# p2n-001.net
KiCad netlist of a schematic drawn in EAGLE
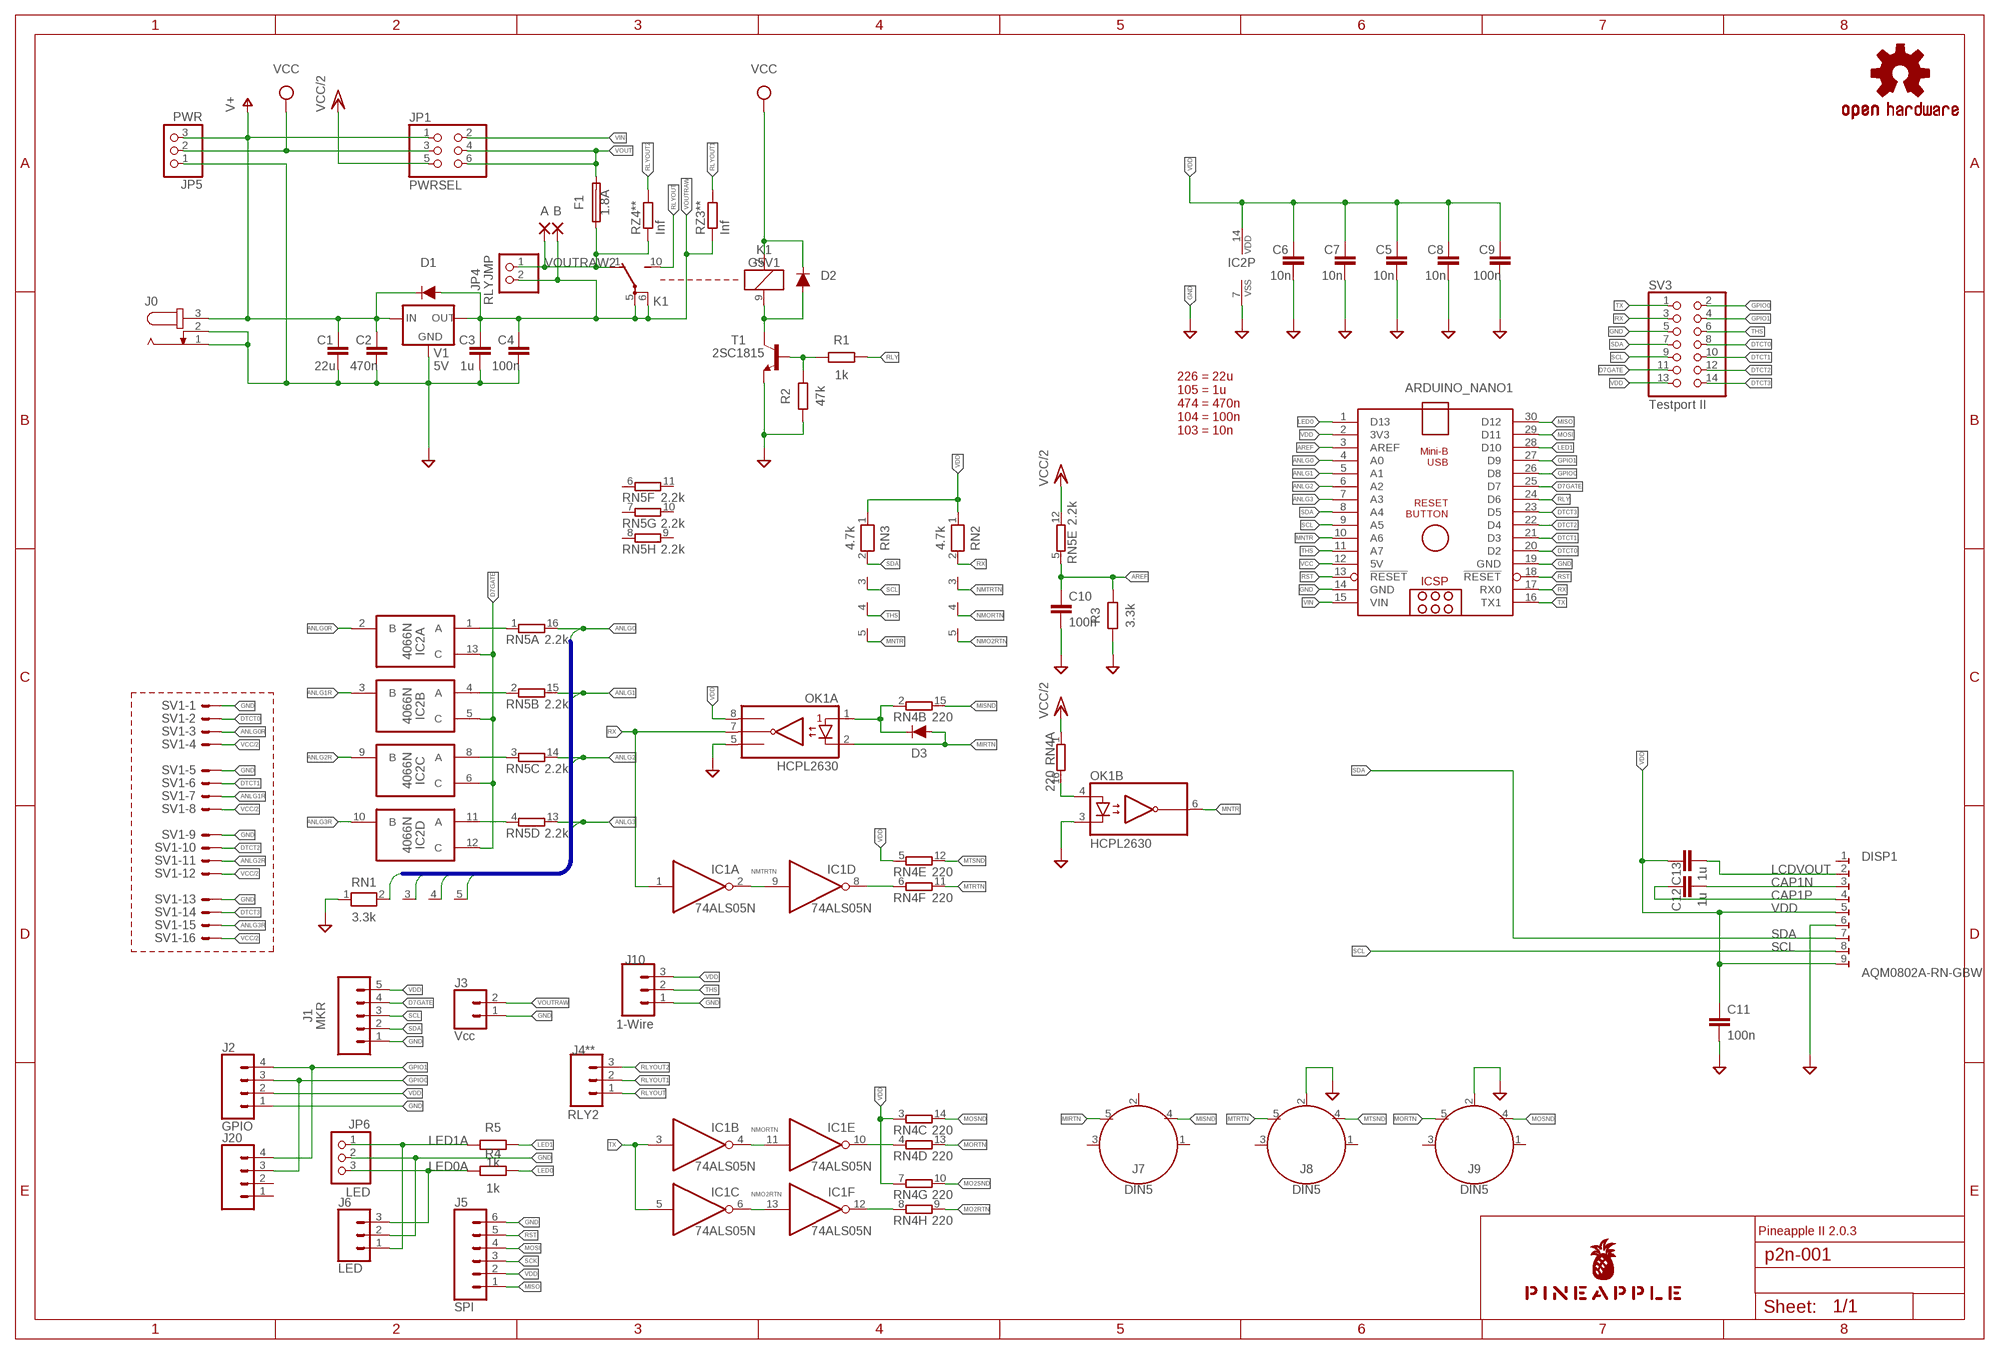
[diagram p0: schematic, sheet 1]

(export (version "E")
  (design (tool "Eeschema 10.0.6"))
  (components
    (comp (ref "A")
      (value "SMD2")
      (footprint "eagle-import:SMD1,27-2,54")
      (libsource (lib "eagle-import") (part "SMD2"))
    )
    (comp (ref "ARDUINO_NANO1")
      (value "ARDUINO_NANO")
      (footprint "eagle-import:ARDUINO_NANO")
      (libsource (lib "eagle-import") (part "ARDUINO_NANO"))
    )
    (comp (ref "B")
      (value "SMD2")
      (footprint "eagle-import:SMD1,27-2,54")
      (libsource (lib "eagle-import") (part "SMD2"))
    )
    (comp (ref "C1")
      (value "22u")
      (footprint "eagle-import:C025-050X050")
      (libsource (lib "eagle-import") (part "C-EU025-050X050"))
    )
    (comp (ref "C2")
      (value "470n")
      (footprint "eagle-import:C050-024X044")
      (libsource (lib "eagle-import") (part "C-EU050-024X044"))
    )
    (comp (ref "C3")
      (value "1u")
      (footprint "eagle-import:C050-024X044")
      (libsource (lib "eagle-import") (part "C-EU050-024X044"))
    )
    (comp (ref "C4")
      (value "100n")
      (footprint "eagle-import:C025-024X044")
      (libsource (lib "eagle-import") (part "C-EU025-024X044"))
    )
    (comp (ref "C5")
      (value "10n")
      (footprint "eagle-import:C025-024X044")
      (libsource (lib "eagle-import") (part "resistor_348_C-EU025-024X044"))
    )
    (comp (ref "C6")
      (value "10n")
      (footprint "eagle-import:C025-024X044")
      (libsource (lib "eagle-import") (part "resistor_348_C-EU025-024X044"))
    )
    (comp (ref "C7")
      (value "10n")
      (footprint "eagle-import:C025-024X044")
      (libsource (lib "eagle-import") (part "resistor_348_C-EU025-024X044"))
    )
    (comp (ref "C8")
      (value "10n")
      (footprint "eagle-import:C025-024X044")
      (libsource (lib "eagle-import") (part "resistor_348_C-EU025-024X044"))
    )
    (comp (ref "C9")
      (value "100n")
      (footprint "eagle-import:C025-024X044")
      (libsource (lib "eagle-import") (part "resistor_348_C-EU025-024X044"))
    )
    (comp (ref "C10")
      (value "100n")
      (footprint "eagle-import:C025-024X044")
      (libsource (lib "eagle-import") (part "C-EU025-024X044"))
    )
    (comp (ref "C11")
      (value "100n")
      (footprint "eagle-import:C025-024X044")
      (libsource (lib "eagle-import") (part "C-EU025-024X044"))
    )
    (comp (ref "C12")
      (value "1u")
      (footprint "eagle-import:C050-024X044")
      (libsource (lib "eagle-import") (part "C-EU050-024X044"))
    )
    (comp (ref "C13")
      (value "1u")
      (footprint "eagle-import:C050-024X044")
      (libsource (lib "eagle-import") (part "C-EU050-024X044"))
    )
    (comp (ref "D1")
      (value "DIODE-1N4148")
      (footprint "eagle-import:DIODE-1N4148")
      (libsource (lib "eagle-import") (part "DIODE-1N4148"))
    )
    (comp (ref "D2")
      (value "DIODE-1N4148")
      (footprint "eagle-import:DIODE-1N4148")
      (libsource (lib "eagle-import") (part "DIODE-1N4148"))
    )
    (comp (ref "D3")
      (value "DIODE-1N4148")
      (footprint "eagle-import:DIODE-1N4148")
      (libsource (lib "eagle-import") (part "DIODE-1N4148"))
    )
    (comp (ref "DISP1")
      (value "AQM0802A-RN-GBW")
      (footprint "eagle-import:AQM0802A-RN-GBW-FOOTPRINT")
      (libsource (lib "eagle-import") (part "AQM0802A-RN-GBW"))
    )
    (comp (ref "F1")
      (value "1.8A")
      (footprint "eagle-import:TE5")
      (libsource (lib "eagle-import") (part "TE5"))
    )
    (comp (ref "IC1")
      (value "74ALS05N")
      (footprint "eagle-import:DIL14")
      (libsource (lib "eagle-import") (part "7405NALS"))
    )
    (comp (ref "IC2")
      (value "4066N")
      (footprint "eagle-import:DIL14")
      (libsource (lib "eagle-import") (part "4066N"))
    )
    (comp (ref "J0")
      (value "JACK-PLUG0")
      (footprint "eagle-import:SPC4077")
      (libsource (lib "eagle-import") (part "JACK-PLUG0"))
    )
    (comp (ref "J1")
      (value "MKR")
      (footprint "eagle-import:JST-5-PTH")
      (libsource (lib "eagle-import") (part "CONN_05JST"))
    )
    (comp (ref "J2")
      (value "GPIO")
      (footprint "eagle-import:JST-4-PTH")
      (libsource (lib "eagle-import") (part "CONN_04JST-PTH"))
    )
    (comp (ref "J3")
      (value "Vcc")
      (footprint "eagle-import:JST-2-PTH")
      (libsource (lib "eagle-import") (part "CONN_02JST-PTH-2"))
    )
    (comp (ref "J4**")
      (value "RLY2")
      (footprint "eagle-import:JST-3-PTH-NS")
      (libsource (lib "eagle-import") (part "CONN_03JST-PTH-NS"))
    )
    (comp (ref "J5")
      (value "SPI")
      (footprint "eagle-import:1X06_1.27MM")
      (libsource (lib "eagle-import") (part "CONN_061.27MM"))
    )
    (comp (ref "J6")
      (value "LED")
      (footprint "eagle-import:JST-3-PTH-VERT")
      (libsource (lib "eagle-import") (part "CONN_03JST-PTH-VERT"))
    )
    (comp (ref "J7")
      (value "DIN5")
      (footprint "eagle-import:DIN5-RA-PTH")
      (libsource (lib "eagle-import") (part "DIN5"))
    )
    (comp (ref "J8")
      (value "DIN5")
      (footprint "eagle-import:DIN5-RA-PTH")
      (libsource (lib "eagle-import") (part "DIN5"))
    )
    (comp (ref "J9")
      (value "DIN5")
      (footprint "eagle-import:DIN5-RA-PTH")
      (libsource (lib "eagle-import") (part "DIN5"))
    )
    (comp (ref "J10")
      (value "1-Wire")
      (footprint "eagle-import:JST-3-PTH-VERT")
      (libsource (lib "eagle-import") (part "CONN_03JST-PTH-VERT"))
    )
    (comp (ref "J20")
      (value "CONN_041.27MM")
      (footprint "eagle-import:1X04_1.27MM")
      (libsource (lib "eagle-import") (part "CONN_041.27MM"))
    )
    (comp (ref "JP1")
      (value "PWRSEL")
      (footprint "eagle-import:2X03")
      (libsource (lib "eagle-import") (part "PINHD-2X3"))
    )
    (comp (ref "JP4")
      (value "RLYJMP")
      (footprint "eagle-import:1X02")
      (libsource (lib "eagle-import") (part "PINHD-1X2"))
    )
    (comp (ref "JP5")
      (value "PWR")
      (footprint "eagle-import:1X03")
      (libsource (lib "eagle-import") (part "PINHD-1X3"))
    )
    (comp (ref "JP6")
      (value "LED")
      (footprint "eagle-import:1X03")
      (libsource (lib "eagle-import") (part "PINHD-1X3"))
    )
    (comp (ref "K1")
      (value "G5V1")
      (footprint "eagle-import:G5V1")
      (fields (field (name "MPN") "G5V-1-DC24"))
      (libsource (lib "eagle-import") (part "G5V1"))
    )
    (comp (ref "LOGO1")
      (value "OSHW-LOGOS-COPPER")
      (footprint "eagle-import:OSHW-LOGO-S_COPPER")
      (libsource (lib "eagle-import") (part "OSHW-LOGOS-COPPER"))
    )
    (comp (ref "OK1")
      (value "HCPL2630")
      (footprint "eagle-import:DIL08")
      (fields (field (name "MF") "AGILENT TECHNOLOGIES") (field (name "MPN") "HCPL-2630-000E"))
      (libsource (lib "eagle-import") (part "HCPL2630"))
    )
    (comp (ref "R1")
      (value "1k")
      (footprint "eagle-import:0204_5")
      (libsource (lib "eagle-import") (part "resistor_348_R-EU_0204/5"))
    )
    (comp (ref "R2")
      (value "47k")
      (footprint "eagle-import:0204_5")
      (libsource (lib "eagle-import") (part "resistor_348_R-EU_0204/5"))
    )
    (comp (ref "R3")
      (value "3.3k")
      (footprint "eagle-import:0204_5")
      (libsource (lib "eagle-import") (part "resistor_348_R-EU_0204/5"))
    )
    (comp (ref "R4")
      (value "1k")
      (footprint "eagle-import:0204_5")
      (libsource (lib "eagle-import") (part "resistor_348_R-EU_0204/5"))
    )
    (comp (ref "R5")
      (value "1k")
      (footprint "eagle-import:0204_5")
      (libsource (lib "eagle-import") (part "resistor_348_R-EU_0204/5"))
    )
    (comp (ref "RN1")
      (value "3.3k")
      (footprint "eagle-import:RN-5")
      (libsource (lib "eagle-import") (part "RN04"))
    )
    (comp (ref "RN2")
      (value "4.7k")
      (footprint "eagle-import:RN-5")
      (libsource (lib "eagle-import") (part "RN04"))
    )
    (comp (ref "RN3")
      (value "4.7k")
      (footprint "eagle-import:RN-5")
      (libsource (lib "eagle-import") (part "RN04"))
    )
    (comp (ref "RN4")
      (value "220")
      (footprint "eagle-import:DIL16")
      (libsource (lib "eagle-import") (part "8R-N"))
    )
    (comp (ref "RN5")
      (value "2.2k")
      (footprint "eagle-import:DIL16")
      (libsource (lib "eagle-import") (part "8R-N"))
    )
    (comp (ref "RZ3**")
      (value "Inf")
      (footprint "eagle-import:M2012")
      (libsource (lib "eagle-import") (part "R-EU_M2012"))
    )
    (comp (ref "RZ4**")
      (value "Inf")
      (footprint "eagle-import:M2012")
      (libsource (lib "eagle-import") (part "R-EU_M2012"))
    )
    (comp (ref "SV1")
      (value "ML16LE")
      (footprint "eagle-import:ML16L")
      (libsource (lib "eagle-import") (part "ML16LE"))
    )
    (comp (ref "SV3")
      (value "Testport II")
      (footprint "eagle-import:2X07")
      (libsource (lib "eagle-import") (part "PINHD-2X7"))
    )
    (comp (ref "T1")
      (value "2SC1815")
      (footprint "eagle-import:TO92-ECB")
      (libsource (lib "eagle-import") (part "2SC1815"))
    )
    (comp (ref "U$1")
      (value "PINEAPPLE450_SILK")
      (footprint "eagle-import:PINEAPPLE450_SILK")
      (libsource (lib "eagle-import") (part "PINEAPPLE450_SILK"))
    )
    (comp (ref "V1")
      (value "5V")
      (footprint "eagle-import:78XXL")
      (libsource (lib "eagle-import") (part "78XXL"))
    )
  )
  (nets
    (net (code "1") (name "/CAP1N") (class "Default")
      (node (ref "C12") (pin "2") (pinfunction "2_2") (pintype "passive"))
      (node (ref "DISP1") (pin "3") (pinfunction "3_3") (pintype "passive"))
    )
    (net (code "2") (name "/CAP1P") (class "Default")
      (node (ref "C12") (pin "1") (pinfunction "1_1") (pintype "passive"))
      (node (ref "DISP1") (pin "4") (pinfunction "4_4") (pintype "passive"))
    )
    (net (code "3") (name "/LCDVOUT") (class "Default")
      (node (ref "C13") (pin "2") (pinfunction "2_2") (pintype "passive"))
      (node (ref "DISP1") (pin "2") (pinfunction "2_2") (pintype "passive"))
    )
    (net (code "4") (name "/LED0A") (class "Default")
      (node (ref "J6") (pin "3") (pinfunction "3_3") (pintype "passive"))
      (node (ref "JP6") (pin "3") (pinfunction "3_3") (pintype "passive"))
      (node (ref "R4") (pin "1") (pinfunction "1_1") (pintype "passive"))
    )
    (net (code "5") (name "/LED1A") (class "Default")
      (node (ref "J6") (pin "1") (pinfunction "1_1") (pintype "passive"))
      (node (ref "JP6") (pin "1") (pinfunction "1_1") (pintype "passive"))
      (node (ref "R5") (pin "1") (pinfunction "1_1") (pintype "passive"))
    )
    (net (code "6") (name "/VOUTRAW2") (class "Default")
      (node (ref "A") (pin "1") (pinfunction "P_1") (pintype "passive"))
      (node (ref "F1") (pin "1") (pinfunction "1_1") (pintype "passive"))
      (node (ref "JP4") (pin "1") (pinfunction "1_1") (pintype "passive"))
      (node (ref "K1") (pin "1") (pinfunction "O_1") (pintype "passive"))
      (node (ref "RZ4**") (pin "1") (pinfunction "1_1") (pintype "passive"))
    )
    (net (code "7") (name "ANLG0") (class "Default")
      (node (ref "ARDUINO_NANO1") (pin "4") (pinfunction "A0_4") (pintype "bidirectional"))
      (node (ref "RN1") (pin "2") (pinfunction "2_2") (pintype "passive"))
      (node (ref "RN5") (pin "16") (pinfunction "2_16") (pintype "passive"))
    )
    (net (code "8") (name "ANLG0R") (class "Default")
      (node (ref "IC2") (pin "2") (pinfunction "B_2") (pintype "tri_state"))
      (node (ref "SV1") (pin "3") (pinfunction "S_3") (pintype "passive"))
    )
    (net (code "9") (name "ANLG1") (class "Default")
      (node (ref "ARDUINO_NANO1") (pin "5") (pinfunction "A1_5") (pintype "bidirectional"))
      (node (ref "RN1") (pin "3") (pinfunction "3_3") (pintype "passive"))
      (node (ref "RN5") (pin "15") (pinfunction "2_15") (pintype "passive"))
    )
    (net (code "10") (name "ANLG1R") (class "Default")
      (node (ref "IC2") (pin "3") (pinfunction "B_3") (pintype "tri_state"))
      (node (ref "SV1") (pin "7") (pinfunction "S_7") (pintype "passive"))
    )
    (net (code "11") (name "ANLG2") (class "Default")
      (node (ref "ARDUINO_NANO1") (pin "6") (pinfunction "A2_6") (pintype "bidirectional"))
      (node (ref "RN1") (pin "4") (pinfunction "4_4") (pintype "passive"))
      (node (ref "RN5") (pin "14") (pinfunction "2_14") (pintype "passive"))
    )
    (net (code "12") (name "ANLG2R") (class "Default")
      (node (ref "IC2") (pin "9") (pinfunction "B_9") (pintype "tri_state"))
      (node (ref "SV1") (pin "11") (pinfunction "S_11") (pintype "passive"))
    )
    (net (code "13") (name "ANLG3") (class "Default")
      (node (ref "ARDUINO_NANO1") (pin "7") (pinfunction "A3_7") (pintype "bidirectional"))
      (node (ref "RN1") (pin "5") (pinfunction "5_5") (pintype "passive"))
      (node (ref "RN5") (pin "13") (pinfunction "2_13") (pintype "passive"))
    )
    (net (code "14") (name "ANLG3R") (class "Default")
      (node (ref "IC2") (pin "10") (pinfunction "B_10") (pintype "tri_state"))
      (node (ref "SV1") (pin "15") (pinfunction "S_15") (pintype "passive"))
    )
    (net (code "15") (name "AREF") (class "Default")
      (node (ref "ARDUINO_NANO1") (pin "3") (pinfunction "AREF_3") (pintype "input"))
      (node (ref "C10") (pin "1") (pinfunction "1_1") (pintype "passive"))
      (node (ref "R3") (pin "2") (pinfunction "2_2") (pintype "passive"))
      (node (ref "RN5") (pin "5") (pinfunction "1_5") (pintype "passive"))
    )
    (net (code "16") (name "D7GATE") (class "Default")
      (node (ref "ARDUINO_NANO1") (pin "25") (pinfunction "D7_25") (pintype "bidirectional"))
      (node (ref "IC2") (pin "12") (pinfunction "C_12") (pintype "input"))
      (node (ref "IC2") (pin "13") (pinfunction "C_13") (pintype "input"))
      (node (ref "IC2") (pin "5") (pinfunction "C_5") (pintype "input"))
      (node (ref "IC2") (pin "6") (pinfunction "C_6") (pintype "input"))
      (node (ref "J1") (pin "4") (pinfunction "4_4") (pintype "passive"))
      (node (ref "SV3") (pin "11") (pinfunction "11_11") (pintype "passive"))
    )
    (net (code "17") (name "DTCT0") (class "Default")
      (node (ref "ARDUINO_NANO1") (pin "20") (pinfunction "D2_20") (pintype "bidirectional"))
      (node (ref "SV1") (pin "2") (pinfunction "S_2") (pintype "passive"))
      (node (ref "SV3") (pin "8") (pinfunction "8_8") (pintype "passive"))
    )
    (net (code "18") (name "DTCT1") (class "Default")
      (node (ref "ARDUINO_NANO1") (pin "21") (pinfunction "D3_21") (pintype "bidirectional"))
      (node (ref "SV1") (pin "6") (pinfunction "S_6") (pintype "passive"))
      (node (ref "SV3") (pin "10") (pinfunction "10_10") (pintype "passive"))
    )
    (net (code "19") (name "DTCT2") (class "Default")
      (node (ref "ARDUINO_NANO1") (pin "22") (pinfunction "D4_22") (pintype "bidirectional"))
      (node (ref "SV1") (pin "10") (pinfunction "S_10") (pintype "passive"))
      (node (ref "SV3") (pin "12") (pinfunction "12_12") (pintype "passive"))
    )
    (net (code "20") (name "DTCT3") (class "Default")
      (node (ref "ARDUINO_NANO1") (pin "23") (pinfunction "D5_23") (pintype "bidirectional"))
      (node (ref "SV1") (pin "14") (pinfunction "S_14") (pintype "passive"))
      (node (ref "SV3") (pin "14") (pinfunction "14_14") (pintype "passive"))
    )
    (net (code "21") (name "GND") (class "Default")
      (node (ref "ARDUINO_NANO1") (pin "14") (pinfunction "GND_14") (pintype "power_in"))
      (node (ref "ARDUINO_NANO1") (pin "19") (pinfunction "GND_19") (pintype "power_in"))
      (node (ref "C1") (pin "2") (pinfunction "2_2") (pintype "passive"))
      (node (ref "C10") (pin "2") (pinfunction "2_2") (pintype "passive"))
      (node (ref "C11") (pin "2") (pinfunction "2_2") (pintype "passive"))
      (node (ref "C2") (pin "2") (pinfunction "2_2") (pintype "passive"))
      (node (ref "C3") (pin "2") (pinfunction "2_2") (pintype "passive"))
      (node (ref "C4") (pin "2") (pinfunction "2_2") (pintype "passive"))
      (node (ref "C5") (pin "2") (pinfunction "2_2") (pintype "passive"))
      (node (ref "C6") (pin "2") (pinfunction "2_2") (pintype "passive"))
      (node (ref "C7") (pin "2") (pinfunction "2_2") (pintype "passive"))
      (node (ref "C8") (pin "2") (pinfunction "2_2") (pintype "passive"))
      (node (ref "C9") (pin "2") (pinfunction "2_2") (pintype "passive"))
      (node (ref "DISP1") (pin "6") (pinfunction "6_6") (pintype "passive"))
      (node (ref "IC2") (pin "7") (pinfunction "VSS_7") (pintype "power_in"))
      (node (ref "J0") (pin "1") (pinfunction "1_1") (pintype "passive"))
      (node (ref "J0") (pin "2") (pinfunction "2_2") (pintype "passive"))
      (node (ref "J1") (pin "1") (pinfunction "1_1") (pintype "passive"))
      (node (ref "J10") (pin "1") (pinfunction "1_1") (pintype "passive"))
      (node (ref "J2") (pin "1") (pinfunction "1_1") (pintype "passive"))
      (node (ref "J3") (pin "1") (pinfunction "1_1") (pintype "passive"))
      (node (ref "J5") (pin "6") (pinfunction "6_6") (pintype "passive"))
      (node (ref "J6") (pin "2") (pinfunction "2_2") (pintype "passive"))
      (node (ref "J8") (pin "2") (pinfunction "2_2") (pintype "bidirectional"))
      (node (ref "J9") (pin "2") (pinfunction "2_2") (pintype "bidirectional"))
      (node (ref "JP5") (pin "1") (pinfunction "1_1") (pintype "passive"))
      (node (ref "JP6") (pin "2") (pinfunction "2_2") (pintype "passive"))
      (node (ref "OK1") (pin "3") (pinfunction "C2_3") (pintype "passive"))
      (node (ref "OK1") (pin "5") (pinfunction "GND_5") (pintype "passive"))
      (node (ref "R2") (pin "1") (pinfunction "1_1") (pintype "passive"))
      (node (ref "R3") (pin "1") (pinfunction "1_1") (pintype "passive"))
      (node (ref "RN1") (pin "1") (pinfunction "1_1") (pintype "passive"))
      (node (ref "SV1") (pin "1") (pinfunction "S_1") (pintype "passive"))
      (node (ref "SV1") (pin "13") (pinfunction "S_13") (pintype "passive"))
      (node (ref "SV1") (pin "5") (pinfunction "S_5") (pintype "passive"))
      (node (ref "SV1") (pin "9") (pinfunction "S_9") (pintype "passive"))
      (node (ref "SV3") (pin "5") (pinfunction "5_5") (pintype "passive"))
      (node (ref "T1") (pin "E") (pinfunction "E_E") (pintype "passive"))
      (node (ref "V1") (pin "GND") (pinfunction "GND_GND") (pintype "input"))
    )
    (net (code "22") (name "GPIO0") (class "Default")
      (node (ref "ARDUINO_NANO1") (pin "26") (pinfunction "D8_26") (pintype "bidirectional"))
      (node (ref "J2") (pin "3") (pinfunction "3_3") (pintype "passive"))
      (node (ref "J20") (pin "3") (pinfunction "3_3") (pintype "passive"))
      (node (ref "SV3") (pin "2") (pinfunction "2_2") (pintype "passive"))
    )
    (net (code "23") (name "GPIO1") (class "Default")
      (node (ref "ARDUINO_NANO1") (pin "27") (pinfunction "D9_27") (pintype "bidirectional"))
      (node (ref "J2") (pin "4") (pinfunction "4_4") (pintype "passive"))
      (node (ref "J20") (pin "4") (pinfunction "4_4") (pintype "passive"))
      (node (ref "SV3") (pin "4") (pinfunction "4_4") (pintype "passive"))
    )
    (net (code "24") (name "LED0") (class "Default")
      (node (ref "ARDUINO_NANO1") (pin "1") (pinfunction "D13_1") (pintype "bidirectional"))
      (node (ref "R4") (pin "2") (pinfunction "2_2") (pintype "passive"))
    )
    (net (code "25") (name "LED1") (class "Default")
      (node (ref "ARDUINO_NANO1") (pin "28") (pinfunction "D10_28") (pintype "bidirectional"))
      (node (ref "R5") (pin "2") (pinfunction "2_2") (pintype "passive"))
    )
    (net (code "26") (name "MIRTN") (class "Default")
      (node (ref "D3") (pin "A") (pinfunction "A_A") (pintype "passive"))
      (node (ref "J7") (pin "5") (pinfunction "5_5") (pintype "bidirectional"))
      (node (ref "OK1") (pin "2") (pinfunction "C1_2") (pintype "passive"))
    )
    (net (code "27") (name "MISND") (class "Default")
      (node (ref "J7") (pin "4") (pinfunction "4_4") (pintype "bidirectional"))
      (node (ref "RN4") (pin "15") (pinfunction "2_15") (pintype "passive"))
    )
    (net (code "28") (name "MISO") (class "Default")
      (node (ref "ARDUINO_NANO1") (pin "30") (pinfunction "D12_30") (pintype "bidirectional"))
      (node (ref "J5") (pin "1") (pinfunction "1_1") (pintype "passive"))
    )
    (net (code "29") (name "MNTR") (class "Default")
      (node (ref "ARDUINO_NANO1") (pin "10") (pinfunction "A6_10") (pintype "bidirectional"))
      (node (ref "OK1") (pin "6") (pinfunction "VO2_6") (pintype "passive"))
      (node (ref "RN3") (pin "5") (pinfunction "5_5") (pintype "passive"))
    )
    (net (code "30") (name "MO2RTN") (class "Default")
      (node (ref "RN4") (pin "9") (pinfunction "2_9") (pintype "passive"))
    )
    (net (code "31") (name "MO2SND") (class "Default")
      (node (ref "RN4") (pin "10") (pinfunction "2_10") (pintype "passive"))
    )
    (net (code "32") (name "MORTN") (class "Default")
      (node (ref "J9") (pin "5") (pinfunction "5_5") (pintype "bidirectional"))
      (node (ref "RN4") (pin "13") (pinfunction "2_13") (pintype "passive"))
    )
    (net (code "33") (name "MOSI") (class "Default")
      (node (ref "ARDUINO_NANO1") (pin "29") (pinfunction "D11_29") (pintype "bidirectional"))
      (node (ref "J5") (pin "4") (pinfunction "4_4") (pintype "passive"))
    )
    (net (code "34") (name "MOSND") (class "Default")
      (node (ref "J9") (pin "4") (pinfunction "4_4") (pintype "bidirectional"))
      (node (ref "RN4") (pin "14") (pinfunction "2_14") (pintype "passive"))
    )
    (net (code "35") (name "MTRTN") (class "Default")
      (node (ref "J8") (pin "5") (pinfunction "5_5") (pintype "bidirectional"))
      (node (ref "RN4") (pin "11") (pinfunction "2_11") (pintype "passive"))
    )
    (net (code "36") (name "MTSND") (class "Default")
      (node (ref "J8") (pin "4") (pinfunction "4_4") (pintype "bidirectional"))
      (node (ref "RN4") (pin "12") (pinfunction "2_12") (pintype "passive"))
    )
    (net (code "37") (name "NMO2RTN") (class "Default")
      (node (ref "IC1") (pin "13") (pinfunction "I_13") (pintype "input"))
      (node (ref "IC1") (pin "6") (pinfunction "O_6") (pintype "open_collector"))
      (node (ref "RN2") (pin "5") (pinfunction "5_5") (pintype "passive"))
    )
    (net (code "38") (name "NMORTN") (class "Default")
      (node (ref "IC1") (pin "11") (pinfunction "I_11") (pintype "input"))
      (node (ref "IC1") (pin "4") (pinfunction "O_4") (pintype "open_collector"))
      (node (ref "RN2") (pin "4") (pinfunction "4_4") (pintype "passive"))
    )
    (net (code "39") (name "NMTRTN") (class "Default")
      (node (ref "IC1") (pin "2") (pinfunction "O_2") (pintype "open_collector"))
      (node (ref "IC1") (pin "9") (pinfunction "I_9") (pintype "input"))
      (node (ref "RN2") (pin "3") (pinfunction "3_3") (pintype "passive"))
    )
    (net (code "40") (name "Net-(IC1D-O)") (class "Default")
      (node (ref "IC1") (pin "8") (pinfunction "O_8") (pintype "open_collector"))
      (node (ref "RN4") (pin "6") (pinfunction "1_6") (pintype "passive"))
    )
    (net (code "41") (name "Net-(IC1E-O)") (class "Default")
      (node (ref "IC1") (pin "10") (pinfunction "O_10") (pintype "open_collector"))
      (node (ref "RN4") (pin "4") (pinfunction "1_4") (pintype "passive"))
    )
    (net (code "42") (name "Net-(IC1F-O)") (class "Default")
      (node (ref "IC1") (pin "12") (pinfunction "O_12") (pintype "open_collector"))
      (node (ref "RN4") (pin "8") (pinfunction "1_8") (pintype "passive"))
    )
    (net (code "43") (name "Net-(IC2A-A)") (class "Default")
      (node (ref "IC2") (pin "1") (pinfunction "A_1") (pintype "tri_state"))
      (node (ref "RN5") (pin "1") (pinfunction "1_1") (pintype "passive"))
    )
    (net (code "44") (name "Net-(IC2B-A)") (class "Default")
      (node (ref "IC2") (pin "4") (pinfunction "A_4") (pintype "tri_state"))
      (node (ref "RN5") (pin "2") (pinfunction "1_2") (pintype "passive"))
    )
    (net (code "45") (name "Net-(IC2C-A)") (class "Default")
      (node (ref "IC2") (pin "8") (pinfunction "A_8") (pintype "tri_state"))
      (node (ref "RN5") (pin "3") (pinfunction "1_3") (pintype "passive"))
    )
    (net (code "46") (name "Net-(IC2D-A)") (class "Default")
      (node (ref "IC2") (pin "11") (pinfunction "A_11") (pintype "tri_state"))
      (node (ref "RN5") (pin "4") (pinfunction "1_4") (pintype "passive"))
    )
    (net (code "47") (name "Net-(K1A-2)") (class "Default")
      (node (ref "D2") (pin "A") (pinfunction "A_A") (pintype "passive"))
      (node (ref "K1") (pin "9") (pinfunction "2_9") (pintype "passive"))
      (node (ref "T1") (pin "C") (pinfunction "C_C") (pintype "passive"))
    )
    (net (code "48") (name "Net-(OK1A-A1)") (class "Default")
      (node (ref "D3") (pin "C") (pinfunction "C_C") (pintype "passive"))
      (node (ref "OK1") (pin "1") (pinfunction "A1_1") (pintype "passive"))
      (node (ref "RN4") (pin "2") (pinfunction "1_2") (pintype "passive"))
    )
    (net (code "49") (name "Net-(OK1B-A2)") (class "Default")
      (node (ref "OK1") (pin "4") (pinfunction "A2_4") (pintype "passive"))
      (node (ref "RN4") (pin "16") (pinfunction "2_16") (pintype "passive"))
    )
    (net (code "50") (name "Net-(R1-Pad1)") (class "Default")
      (node (ref "R1") (pin "1") (pinfunction "1_1") (pintype "passive"))
      (node (ref "R2") (pin "2") (pinfunction "2_2") (pintype "passive"))
      (node (ref "T1") (pin "B") (pinfunction "B_B") (pintype "passive"))
    )
    (net (code "51") (name "RLY") (class "Default")
      (node (ref "ARDUINO_NANO1") (pin "24") (pinfunction "D6_24") (pintype "bidirectional"))
      (node (ref "R1") (pin "2") (pinfunction "2_2") (pintype "passive"))
    )
    (net (code "52") (name "RLYOUT") (class "Default")
      (node (ref "J4**") (pin "1") (pinfunction "1_1") (pintype "passive"))
      (node (ref "K1") (pin "10") (pinfunction "S_10") (pintype "passive"))
    )
    (net (code "53") (name "RLYOUT1") (class "Default")
      (node (ref "J4**") (pin "2") (pinfunction "2_2") (pintype "passive"))
      (node (ref "RZ3**") (pin "2") (pinfunction "2_2") (pintype "passive"))
    )
    (net (code "54") (name "RLYOUT2") (class "Default")
      (node (ref "J4**") (pin "3") (pinfunction "3_3") (pintype "passive"))
      (node (ref "RZ4**") (pin "2") (pinfunction "2_2") (pintype "passive"))
    )
    (net (code "55") (name "RST") (class "Default")
      (node (ref "ARDUINO_NANO1") (pin "13") (pinfunction "~{RESET}_13") (pintype "input"))
      (node (ref "ARDUINO_NANO1") (pin "18") (pinfunction "~{RESET}_18") (pintype "input"))
      (node (ref "J5") (pin "5") (pinfunction "5_5") (pintype "passive"))
    )
    (net (code "56") (name "RX") (class "Default")
      (node (ref "ARDUINO_NANO1") (pin "17") (pinfunction "RX0_17") (pintype "bidirectional"))
      (node (ref "IC1") (pin "1") (pinfunction "I_1") (pintype "input"))
      (node (ref "OK1") (pin "7") (pinfunction "VO1_7") (pintype "passive"))
      (node (ref "RN2") (pin "2") (pinfunction "2_2") (pintype "passive"))
      (node (ref "SV3") (pin "3") (pinfunction "3_3") (pintype "passive"))
    )
    (net (code "57") (name "SCK") (class "Default")
      (node (ref "J5") (pin "3") (pinfunction "3_3") (pintype "passive"))
    )
    (net (code "58") (name "SCL") (class "Default")
      (node (ref "ARDUINO_NANO1") (pin "9") (pinfunction "A5_9") (pintype "bidirectional"))
      (node (ref "DISP1") (pin "8") (pinfunction "8_8") (pintype "passive"))
      (node (ref "J1") (pin "3") (pinfunction "3_3") (pintype "passive"))
      (node (ref "RN3") (pin "3") (pinfunction "3_3") (pintype "passive"))
      (node (ref "SV3") (pin "9") (pinfunction "9_9") (pintype "passive"))
    )
    (net (code "59") (name "SDA") (class "Default")
      (node (ref "ARDUINO_NANO1") (pin "8") (pinfunction "A4_8") (pintype "bidirectional"))
      (node (ref "DISP1") (pin "7") (pinfunction "7_7") (pintype "passive"))
      (node (ref "J1") (pin "2") (pinfunction "2_2") (pintype "passive"))
      (node (ref "RN3") (pin "2") (pinfunction "2_2") (pintype "passive"))
      (node (ref "SV3") (pin "7") (pinfunction "7_7") (pintype "passive"))
    )
    (net (code "60") (name "THS") (class "Default")
      (node (ref "ARDUINO_NANO1") (pin "11") (pinfunction "A7_11") (pintype "bidirectional"))
      (node (ref "J10") (pin "2") (pinfunction "2_2") (pintype "passive"))
      (node (ref "RN3") (pin "4") (pinfunction "4_4") (pintype "passive"))
      (node (ref "SV3") (pin "6") (pinfunction "6_6") (pintype "passive"))
    )
    (net (code "61") (name "TX") (class "Default")
      (node (ref "ARDUINO_NANO1") (pin "16") (pinfunction "TX1_16") (pintype "bidirectional"))
      (node (ref "IC1") (pin "3") (pinfunction "I_3") (pintype "input"))
      (node (ref "IC1") (pin "5") (pinfunction "I_5") (pintype "input"))
      (node (ref "SV3") (pin "1") (pinfunction "1_1") (pintype "passive"))
    )
    (net (code "62") (name "V+") (class "Default")
      (node (ref "C1") (pin "1") (pinfunction "1_1") (pintype "passive"))
      (node (ref "C2") (pin "1") (pinfunction "1_1") (pintype "passive"))
      (node (ref "D1") (pin "C") (pinfunction "C_C") (pintype "passive"))
      (node (ref "J0") (pin "3") (pinfunction "3_3") (pintype "passive"))
      (node (ref "JP1") (pin "1") (pinfunction "1_1") (pintype "passive"))
      (node (ref "JP5") (pin "3") (pinfunction "3_3") (pintype "passive"))
      (node (ref "V1") (pin "IN") (pinfunction "IN_IN") (pintype "input"))
    )
    (net (code "63") (name "VCC") (class "Default")
      (node (ref "ARDUINO_NANO1") (pin "12") (pinfunction "5V_12") (pintype "power_in"))
      (node (ref "D2") (pin "C") (pinfunction "C_C") (pintype "passive"))
      (node (ref "JP1") (pin "3") (pinfunction "3_3") (pintype "passive"))
      (node (ref "JP5") (pin "2") (pinfunction "2_2") (pintype "passive"))
      (node (ref "K1") (pin "2") (pinfunction "1_2") (pintype "passive"))
    )
    (net (code "64") (name "VCC{slash}2") (class "Default")
      (node (ref "JP1") (pin "5") (pinfunction "5_5") (pintype "passive"))
      (node (ref "RN4") (pin "1") (pinfunction "1_1") (pintype "passive"))
      (node (ref "RN5") (pin "12") (pinfunction "2_12") (pintype "passive"))
      (node (ref "SV1") (pin "12") (pinfunction "S_12") (pintype "passive"))
      (node (ref "SV1") (pin "16") (pinfunction "S_16") (pintype "passive"))
      (node (ref "SV1") (pin "4") (pinfunction "S_4") (pintype "passive"))
      (node (ref "SV1") (pin "8") (pinfunction "S_8") (pintype "passive"))
    )
    (net (code "65") (name "VDD") (class "Default")
      (node (ref "ARDUINO_NANO1") (pin "2") (pinfunction "3V3_2") (pintype "output"))
      (node (ref "C11") (pin "1") (pinfunction "1_1") (pintype "passive"))
      (node (ref "C13") (pin "1") (pinfunction "1_1") (pintype "passive"))
      (node (ref "C5") (pin "1") (pinfunction "1_1") (pintype "passive"))
      (node (ref "C6") (pin "1") (pinfunction "1_1") (pintype "passive"))
      (node (ref "C7") (pin "1") (pinfunction "1_1") (pintype "passive"))
      (node (ref "C8") (pin "1") (pinfunction "1_1") (pintype "passive"))
      (node (ref "C9") (pin "1") (pinfunction "1_1") (pintype "passive"))
      (node (ref "DISP1") (pin "5") (pinfunction "5_5") (pintype "passive"))
      (node (ref "DISP1") (pin "9") (pinfunction "9_9") (pintype "passive"))
      (node (ref "IC2") (pin "14") (pinfunction "VDD_14") (pintype "power_in"))
      (node (ref "J1") (pin "5") (pinfunction "5_5") (pintype "passive"))
      (node (ref "J10") (pin "3") (pinfunction "3_3") (pintype "passive"))
      (node (ref "J2") (pin "2") (pinfunction "2_2") (pintype "passive"))
      (node (ref "J5") (pin "2") (pinfunction "2_2") (pintype "passive"))
      (node (ref "OK1") (pin "8") (pinfunction "VCC_8") (pintype "passive"))
      (node (ref "RN2") (pin "1") (pinfunction "1_1") (pintype "passive"))
      (node (ref "RN3") (pin "1") (pinfunction "1_1") (pintype "passive"))
      (node (ref "RN4") (pin "3") (pinfunction "1_3") (pintype "passive"))
      (node (ref "RN4") (pin "5") (pinfunction "1_5") (pintype "passive"))
      (node (ref "RN4") (pin "7") (pinfunction "1_7") (pintype "passive"))
      (node (ref "SV3") (pin "13") (pinfunction "13_13") (pintype "passive"))
    )
    (net (code "66") (name "VIN") (class "Default")
      (node (ref "ARDUINO_NANO1") (pin "15") (pinfunction "VIN_15") (pintype "power_in"))
      (node (ref "JP1") (pin "2") (pinfunction "2_2") (pintype "passive"))
    )
    (net (code "67") (name "VOUT") (class "Default")
      (node (ref "F1") (pin "2") (pinfunction "2_2") (pintype "passive"))
      (node (ref "JP1") (pin "4") (pinfunction "4_4") (pintype "passive"))
      (node (ref "JP1") (pin "6") (pinfunction "6_6") (pintype "passive"))
    )
    (net (code "68") (name "VOUTRAW") (class "Default")
      (node (ref "B") (pin "1") (pinfunction "P_1") (pintype "passive"))
      (node (ref "C3") (pin "1") (pinfunction "1_1") (pintype "passive"))
      (node (ref "C4") (pin "1") (pinfunction "1_1") (pintype "passive"))
      (node (ref "D1") (pin "A") (pinfunction "A_A") (pintype "passive"))
      (node (ref "J3") (pin "2") (pinfunction "2_2") (pintype "passive"))
      (node (ref "JP4") (pin "2") (pinfunction "2_2") (pintype "passive"))
      (node (ref "K1") (pin "5") (pinfunction "P_5") (pintype "passive"))
      (node (ref "K1") (pin "6") (pinfunction "P_6") (pintype "passive"))
      (node (ref "RZ3**") (pin "1") (pinfunction "1_1") (pintype "passive"))
      (node (ref "V1") (pin "OUT") (pinfunction "OUT_OUT") (pintype "passive"))
    )
    (net (code "69") (name "unconnected-(DISP1-Pad1)") (class "Default")
      (node (ref "DISP1") (pin "1") (pinfunction "1_1") (pintype "passive"))
    )
    (net (code "70") (name "unconnected-(J7-Pad1)") (class "Default")
      (node (ref "J7") (pin "1") (pinfunction "1_1") (pintype "bidirectional"))
    )
    (net (code "71") (name "unconnected-(J7-Pad2)") (class "Default")
      (node (ref "J7") (pin "2") (pinfunction "2_2") (pintype "bidirectional"))
    )
    (net (code "72") (name "unconnected-(J7-Pad3)") (class "Default")
      (node (ref "J7") (pin "3") (pinfunction "3_3") (pintype "bidirectional"))
    )
    (net (code "73") (name "unconnected-(J8-Pad1)") (class "Default")
      (node (ref "J8") (pin "1") (pinfunction "1_1") (pintype "bidirectional"))
    )
    (net (code "74") (name "unconnected-(J8-Pad3)") (class "Default")
      (node (ref "J8") (pin "3") (pinfunction "3_3") (pintype "bidirectional"))
    )
    (net (code "75") (name "unconnected-(J9-Pad1)") (class "Default")
      (node (ref "J9") (pin "1") (pinfunction "1_1") (pintype "bidirectional"))
    )
    (net (code "76") (name "unconnected-(J9-Pad3)") (class "Default")
      (node (ref "J9") (pin "3") (pinfunction "3_3") (pintype "bidirectional"))
    )
    (net (code "77") (name "unconnected-(J20-Pad1)") (class "Default")
      (node (ref "J20") (pin "1") (pinfunction "1_1") (pintype "passive"))
    )
    (net (code "78") (name "unconnected-(J20-Pad2)") (class "Default")
      (node (ref "J20") (pin "2") (pinfunction "2_2") (pintype "passive"))
    )
    (net (code "79") (name "unconnected-(RN5F-1-Pad6)") (class "Default")
      (node (ref "RN5") (pin "6") (pinfunction "1_6") (pintype "passive"))
    )
    (net (code "80") (name "unconnected-(RN5F-2-Pad11)") (class "Default")
      (node (ref "RN5") (pin "11") (pinfunction "2_11") (pintype "passive"))
    )
    (net (code "81") (name "unconnected-(RN5G-1-Pad7)") (class "Default")
      (node (ref "RN5") (pin "7") (pinfunction "1_7") (pintype "passive"))
    )
    (net (code "82") (name "unconnected-(RN5G-2-Pad10)") (class "Default")
      (node (ref "RN5") (pin "10") (pinfunction "2_10") (pintype "passive"))
    )
    (net (code "83") (name "unconnected-(RN5H-1-Pad8)") (class "Default")
      (node (ref "RN5") (pin "8") (pinfunction "1_8") (pintype "passive"))
    )
    (net (code "84") (name "unconnected-(RN5H-2-Pad9)") (class "Default")
      (node (ref "RN5") (pin "9") (pinfunction "2_9") (pintype "passive"))
    )
  )
)
